# esquematico.net
KiCad netlist of a schematic drawn in EAGLE
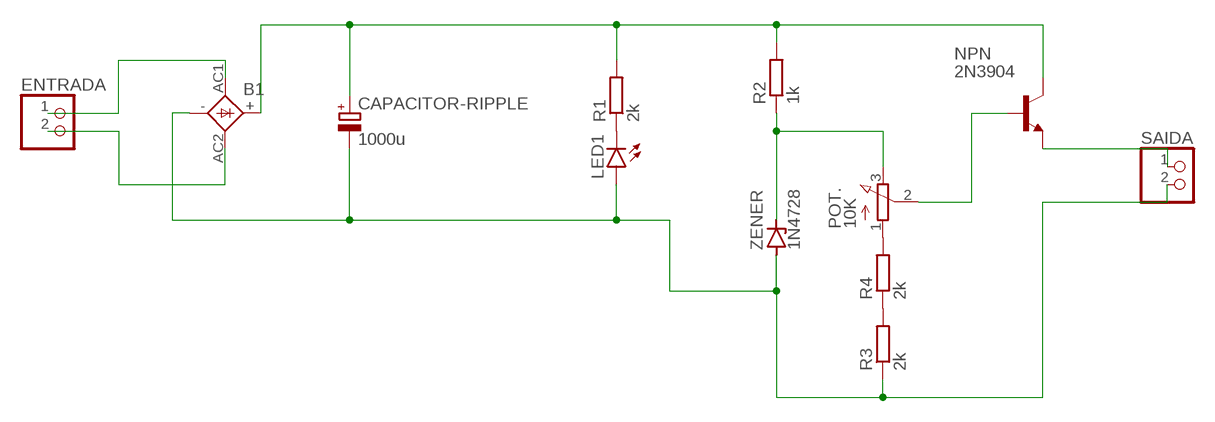
[diagram p0: schematic, sheet 1]

(export (version "E")
  (design (tool "Eeschema 10.0.6"))
  (components
    (comp (ref "B1")
      (value "1KAB")
      (footprint "eagle-import:1KAB")
      (libsource (lib "eagle-import") (part "1KAB"))
    )
    (comp (ref "CAPACITOR-RIPPLE")
      (value "1000u")
      (footprint "eagle-import:E5-10,5")
      (libsource (lib "eagle-import") (part "CPOL-EUE5-10.5"))
    )
    (comp (ref "ENTRADA")
      (value "PINHD-1X2")
      (footprint "eagle-import:1X02")
      (libsource (lib "eagle-import") (part "PINHD-1X2"))
    )
    (comp (ref "LED1")
      (value "LED5MM")
      (footprint "eagle-import:LED5MM")
      (libsource (lib "eagle-import") (part "LED5MM"))
    )
    (comp (ref "NPN")
      (value "2N3904")
      (footprint "eagle-import:TO92")
      (libsource (lib "eagle-import") (part "2N3904"))
    )
    (comp (ref "POT.")
      (value "10K")
      (footprint "eagle-import:3RP_1610N")
      (libsource (lib "eagle-import") (part "3RP/1610N"))
    )
    (comp (ref "R1")
      (value "2k")
      (footprint "eagle-import:0204_7")
      (libsource (lib "eagle-import") (part "R-EU_0204/7"))
    )
    (comp (ref "R2")
      (value "1k")
      (footprint "eagle-import:0204_7")
      (libsource (lib "eagle-import") (part "R-EU_0204/7"))
    )
    (comp (ref "R3")
      (value "2k")
      (footprint "eagle-import:0204_7")
      (libsource (lib "eagle-import") (part "R-EU_0204/7"))
    )
    (comp (ref "R4")
      (value "2k")
      (footprint "eagle-import:0204_7")
      (libsource (lib "eagle-import") (part "R-EU_0204/7"))
    )
    (comp (ref "SAIDA")
      (value "PINHD-1X2")
      (footprint "eagle-import:1X02")
      (libsource (lib "eagle-import") (part "PINHD-1X2"))
    )
    (comp (ref "ZENER")
      (value "1N4728")
      (footprint "eagle-import:DO41Z10")
      (libsource (lib "eagle-import") (part "1N4728"))
    )
  )
  (nets
    (net (code "1") (name "Net-(B1-Pad-)") (class "Default")
      (node (ref "B1") (pin "-") (pinfunction "-_-") (pintype "passive"))
      (node (ref "CAPACITOR-RIPPLE") (pin "-") (pinfunction "-_-") (pintype "passive"))
      (node (ref "LED1") (pin "A") (pinfunction "A_A") (pintype "passive"))
      (node (ref "R3") (pin "1") (pinfunction "1_1") (pintype "passive"))
      (node (ref "SAIDA") (pin "2") (pinfunction "2_2") (pintype "passive"))
      (node (ref "ZENER") (pin "A") (pinfunction "A_A") (pintype "passive"))
    )
    (net (code "2") (name "Net-(B1-PadAC1)") (class "Default")
      (node (ref "B1") (pin "AC1") (pinfunction "AC1_AC1") (pintype "passive"))
      (node (ref "ENTRADA") (pin "1") (pinfunction "1_1") (pintype "passive"))
    )
    (net (code "3") (name "Net-(B1-PadAC2)") (class "Default")
      (node (ref "B1") (pin "AC2") (pinfunction "AC2_AC2") (pintype "passive"))
      (node (ref "ENTRADA") (pin "2") (pinfunction "2_2") (pintype "passive"))
    )
    (net (code "4") (name "Net-(LED1-C)") (class "Default")
      (node (ref "LED1") (pin "K") (pinfunction "C_K") (pintype "passive"))
      (node (ref "R1") (pin "1") (pinfunction "1_1") (pintype "passive"))
    )
    (net (code "5") (name "Net-(NPN-B)") (class "Default")
      (node (ref "NPN") (pin "2") (pinfunction "B_2") (pintype "passive"))
      (node (ref "POT.") (pin "2") (pinfunction "S_2") (pintype "passive"))
    )
    (net (code "6") (name "Net-(NPN-C)") (class "Default")
      (node (ref "B1") (pin "+") (pinfunction "+_+") (pintype "passive"))
      (node (ref "CAPACITOR-RIPPLE") (pin "+") (pinfunction "+_+") (pintype "passive"))
      (node (ref "NPN") (pin "1") (pinfunction "C_1") (pintype "passive"))
      (node (ref "R1") (pin "2") (pinfunction "2_2") (pintype "passive"))
      (node (ref "R2") (pin "2") (pinfunction "2_2") (pintype "passive"))
    )
    (net (code "7") (name "Net-(NPN-E)") (class "Default")
      (node (ref "NPN") (pin "3") (pinfunction "E_3") (pintype "passive"))
      (node (ref "SAIDA") (pin "1") (pinfunction "1_1") (pintype "passive"))
    )
    (net (code "8") (name "Net-(POT.-A)") (class "Default")
      (node (ref "POT.") (pin "1") (pinfunction "A_1") (pintype "passive"))
      (node (ref "R4") (pin "2") (pinfunction "2_2") (pintype "passive"))
    )
    (net (code "9") (name "Net-(POT.-E)") (class "Default")
      (node (ref "POT.") (pin "3") (pinfunction "E_3") (pintype "passive"))
      (node (ref "R2") (pin "1") (pinfunction "1_1") (pintype "passive"))
      (node (ref "ZENER") (pin "C") (pinfunction "C_C") (pintype "passive"))
    )
    (net (code "10") (name "Net-(R3-Pad2)") (class "Default")
      (node (ref "R3") (pin "2") (pinfunction "2_2") (pintype "passive"))
      (node (ref "R4") (pin "1") (pinfunction "1_1") (pintype "passive"))
    )
  )
)
